# dep-switches.net
KiCad netlist of a schematic drawn in Altium Designer
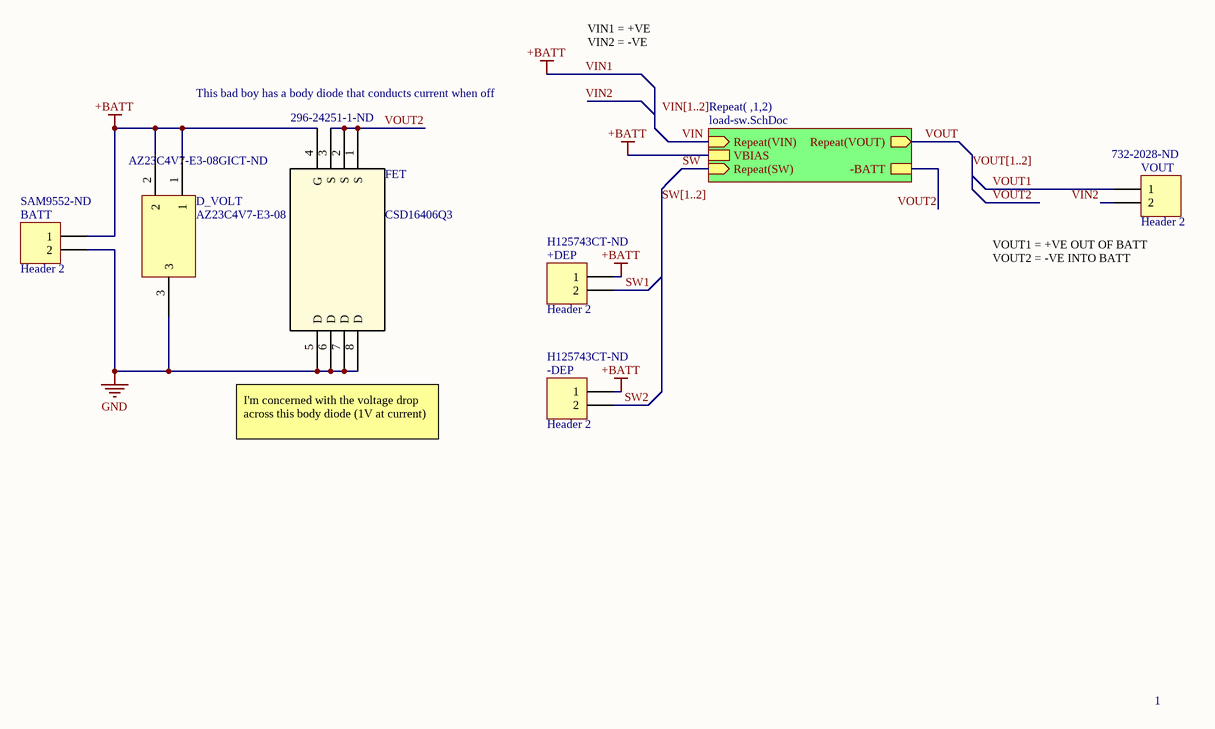
[diagram p0: dep-switches.SchDoc]

(export (version "E")
  (design (tool "Eeschema 10.0.6"))
  (components
    (comp (ref "+DEP")
      (value "Header 2")
      (footprint "DF13A-2P-1.25H(21)")
      (description "Header, 2-Pin")
      (fields
        (field (name "SUPPLIER PART NUMBER 1") "H125743CT-ND")
        (field (name "MANUFACTURER") "Hirose")
        (field (name "MANUFACTURER PART NUMBER") "DF13A-2P-1.25H(21)")
        (field (name "PUBLISHER") "Altium Limited")
      )
      (libsource (lib "Miscellaneous Connectors") (part "Header 2"))
    )
    (comp (ref "-DEP")
      (value "Header 2")
      (footprint "DF13A-2P-1.25H(21)")
      (description "Header, 2-Pin")
      (fields
        (field (name "SUPPLIER PART NUMBER 1") "H125743CT-ND")
        (field (name "MANUFACTURER") "Hirose")
        (field (name "MANUFACTURER PART NUMBER") "DF13A-2P-1.25H(21)")
        (field (name "PUBLISHER") "Altium Limited")
      )
      (libsource (lib "Miscellaneous Connectors") (part "Header 2"))
    )
    (comp (ref "BATT")
      (value "Header 2")
      (footprint "SAM9552-ND")
      (description "Header, 2-Pin")
      (fields
        (field (name "SUPPLIER PART NUMBER 1") "SAM9552-ND")
        (field (name "MANUFACTURER") "Samtec")
        (field (name "MANUFACTURER PART NUMBER") "IPBT-102-H1-T-S-RA-K")
        (field (name "PUBLISHER") "Altium Limited")
      )
      (libsource (lib "Miscellaneous Connectors") (part "Header 2"))
    )
    (comp (ref "D_VOLT")
      (value "AZ23C4V7-E3-08")
      (description "300mW zener diode")
      (fields
        (field (name "SUPPLIER PART NUMBER 1") "AZ23C4V7-E3-08GICT-ND")
        (field (name "MANUFACTURER") "Vishay")
        (field (name "TOLERANCE") "5%")
      )
      (libsource (lib "heron-general") (part "AZ23C4V7-E3-08"))
    )
    (comp (ref "FET")
      (value "CSD16406Q3")
      (footprint "CSD16406Q3")
      (description "Power MOSFET")
      (fields
        (field (name "SUPPLIER PART NUMBER 1") "296-24251-1-ND")
        (field (name "MANUFACTURER") "Texas Instruments")
      )
      (libsource (lib "heron-general") (part "CSD16406Q3"))
    )
    (comp (ref "VOUT")
      (value "Header 2")
      (footprint "CON2_SCREW_5.00MM_691102710002")
      (description "Header, 2-Pin")
      (fields
        (field (name "SUPPLIER PART NUMBER 1") "732-2028-ND")
        (field (name "MANUFACTURER") "Wurth Electronics")
        (field (name "MANUFACTURER PART NUMBER") "691102710002")
        (field (name "PUBLISHER") "Altium Limited")
      )
      (libsource (lib "") (part "Header 2_1"))
    )
  )
  (nets
    (net (code "1") (name "+BATT") (class "Default")
      (node (ref "+DEP") (pin "1") (pinfunction "1_1") (pintype "passive"))
      (node (ref "-DEP") (pin "1") (pinfunction "1_1") (pintype "passive"))
      (node (ref "BATT") (pin "1") (pinfunction "1_1") (pintype "passive"))
      (node (ref "D_VOLT") (pin "1") (pinfunction "1_1") (pintype "passive"))
      (node (ref "D_VOLT") (pin "2") (pinfunction "2_2") (pintype "passive"))
      (node (ref "FET") (pin "4") (pinfunction "G_4") (pintype "passive"))
    )
    (net (code "3") (name "/SW1") (class "Default")
      (node (ref "+DEP") (pin "2") (pinfunction "2_2") (pintype "passive"))
    )
    (net (code "4") (name "/SW2") (class "Default")
      (node (ref "-DEP") (pin "2") (pinfunction "2_2") (pintype "passive"))
    )
    (net (code "7") (name "/VIN2") (class "Default")
      (node (ref "VOUT") (pin "2") (pinfunction "2_2") (pintype "passive"))
    )
    (net (code "10") (name "/VOUT1") (class "Default")
      (node (ref "VOUT") (pin "1") (pinfunction "1_1") (pintype "passive"))
    )
    (net (code "11") (name "/VOUT2") (class "Default")
      (node (ref "FET") (pin "1") (pinfunction "S_1") (pintype "passive"))
      (node (ref "FET") (pin "2") (pinfunction "S_2") (pintype "passive"))
      (node (ref "FET") (pin "3") (pinfunction "S_3") (pintype "passive"))
    )
    (net (code "13") (name "GND") (class "Default")
      (node (ref "BATT") (pin "2") (pinfunction "2_2") (pintype "passive"))
      (node (ref "D_VOLT") (pin "3") (pinfunction "3_3") (pintype "passive"))
      (node (ref "FET") (pin "5") (pinfunction "D_5") (pintype "passive"))
      (node (ref "FET") (pin "6") (pinfunction "D_6") (pintype "passive"))
      (node (ref "FET") (pin "7") (pinfunction "D_7") (pintype "passive"))
      (node (ref "FET") (pin "8") (pinfunction "D_8") (pintype "passive"))
    )
  )
)
